# Loginator2368.net
KiCad netlist of a schematic drawn in EAGLE
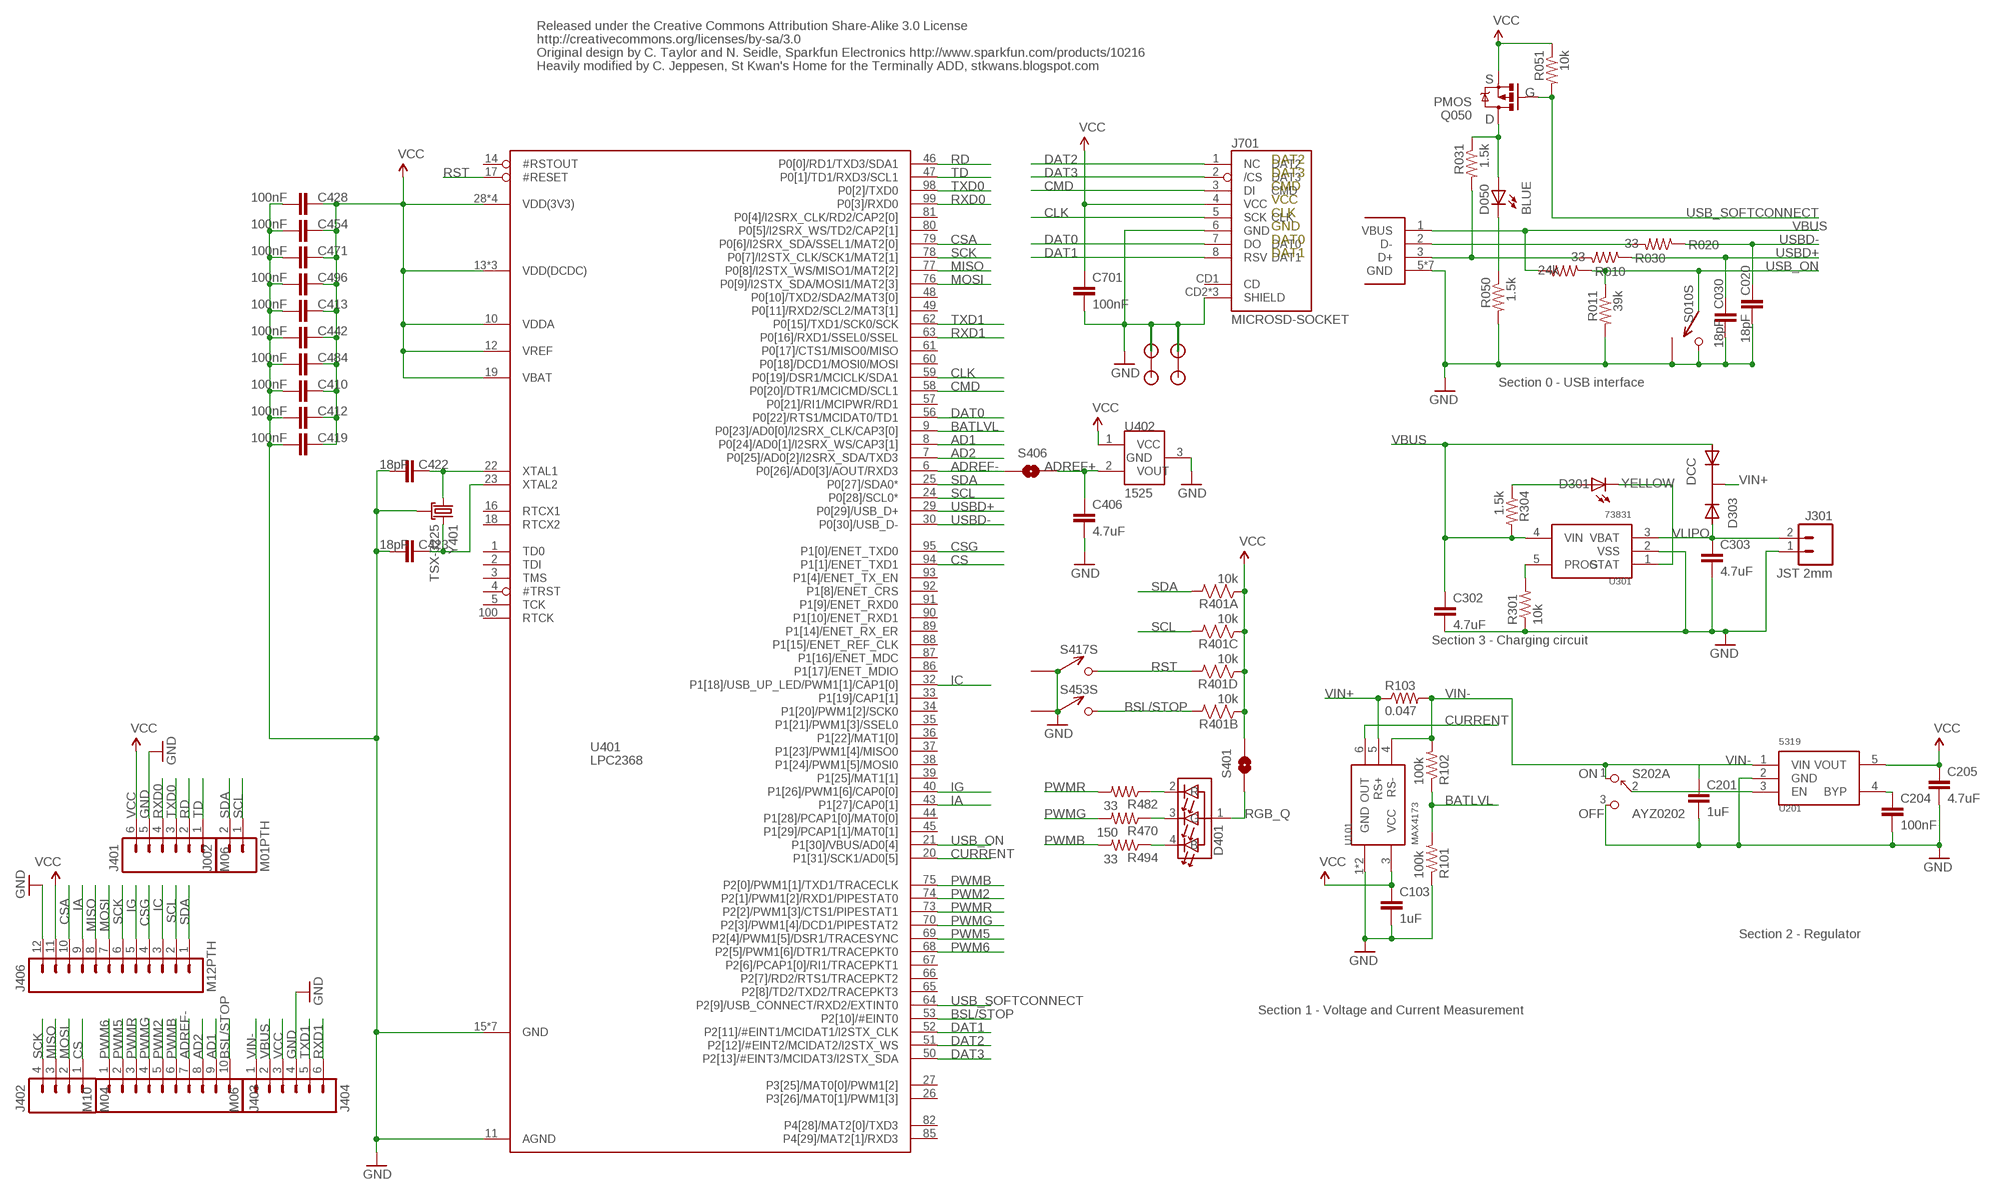
[diagram p0: schematic, sheet 1]

(export (version "E")
  (design (tool "Eeschema 10.0.6"))
  (components
    (comp (ref "C020")
      (value "18pF")
      (footprint "eagle-import:0402-CAP")
      (libsource (lib "eagle-import") (part "CAP0402-CAP"))
    )
    (comp (ref "C030")
      (value "18pF")
      (footprint "eagle-import:0402-CAP")
      (libsource (lib "eagle-import") (part "CAP0402-CAP"))
    )
    (comp (ref "C103")
      (value "1uF")
      (footprint "eagle-import:0402-CAP")
      (libsource (lib "eagle-import") (part "CAP0402-CAP"))
    )
    (comp (ref "C201")
      (value "1uF")
      (footprint "eagle-import:0402-CAP")
      (libsource (lib "eagle-import") (part "CAP0402-CAP"))
    )
    (comp (ref "C204")
      (value "100nF")
      (footprint "eagle-import:0402-CAP")
      (libsource (lib "eagle-import") (part "CAP0402-CAP"))
    )
    (comp (ref "C205")
      (value "4.7uF")
      (footprint "eagle-import:0402-CAP")
      (libsource (lib "eagle-import") (part "CAP0402-CAP"))
    )
    (comp (ref "C302")
      (value "4.7uF")
      (footprint "eagle-import:0402-CAP")
      (libsource (lib "eagle-import") (part "CAP0402-CAP"))
    )
    (comp (ref "C303")
      (value "4.7uF")
      (footprint "eagle-import:0402-CAP")
      (libsource (lib "eagle-import") (part "CAP0402-CAP"))
    )
    (comp (ref "C406")
      (value "4.7uF")
      (footprint "eagle-import:0402-CAP")
      (libsource (lib "eagle-import") (part "CAP0402-CAP"))
    )
    (comp (ref "C410")
      (value "100nF")
      (footprint "eagle-import:0402-CAP")
      (libsource (lib "eagle-import") (part "CAP0402-CAP"))
    )
    (comp (ref "C412")
      (value "100nF")
      (footprint "eagle-import:0402-CAP")
      (libsource (lib "eagle-import") (part "CAP0402-CAP"))
    )
    (comp (ref "C413")
      (value "100nF")
      (footprint "eagle-import:0402-CAP")
      (libsource (lib "eagle-import") (part "CAP0402-CAP"))
    )
    (comp (ref "C419")
      (value "100nF")
      (footprint "eagle-import:0402-CAP")
      (libsource (lib "eagle-import") (part "CAP0402-CAP"))
    )
    (comp (ref "C422")
      (value "18pF")
      (footprint "eagle-import:0402-CAP")
      (libsource (lib "eagle-import") (part "CAP0402-CAP"))
    )
    (comp (ref "C423")
      (value "18pF")
      (footprint "eagle-import:0402-CAP")
      (libsource (lib "eagle-import") (part "CAP0402-CAP"))
    )
    (comp (ref "C428")
      (value "100nF")
      (footprint "eagle-import:0402-CAP")
      (libsource (lib "eagle-import") (part "CAP0402-CAP"))
    )
    (comp (ref "C442")
      (value "100nF")
      (footprint "eagle-import:0402-CAP")
      (libsource (lib "eagle-import") (part "CAP0402-CAP"))
    )
    (comp (ref "C454")
      (value "100nF")
      (footprint "eagle-import:0402-CAP")
      (libsource (lib "eagle-import") (part "CAP0402-CAP"))
    )
    (comp (ref "C471")
      (value "100nF")
      (footprint "eagle-import:0402-CAP")
      (libsource (lib "eagle-import") (part "CAP0402-CAP"))
    )
    (comp (ref "C484")
      (value "100nF")
      (footprint "eagle-import:0402-CAP")
      (libsource (lib "eagle-import") (part "CAP0402-CAP"))
    )
    (comp (ref "C496")
      (value "100nF")
      (footprint "eagle-import:0402-CAP")
      (libsource (lib "eagle-import") (part "CAP0402-CAP"))
    )
    (comp (ref "C701")
      (value "100nF")
      (footprint "eagle-import:0402-CAP")
      (libsource (lib "eagle-import") (part "CAP0402-CAP"))
    )
    (comp (ref "D050")
      (value "BLUE")
      (footprint "eagle-import:LED-0603")
      (libsource (lib "eagle-import") (part "LED0603"))
    )
    (comp (ref "D301")
      (value "YELLOW")
      (footprint "eagle-import:LED-0603")
      (libsource (lib "eagle-import") (part "LED0603"))
    )
    (comp (ref "D303")
      (value "DCC")
      (footprint "eagle-import:SOT-23-3")
      (libsource (lib "eagle-import") (part "PMEG2005CT"))
    )
    (comp (ref "D401")
      (value "RGB")
      (footprint "eagle-import:HSMF-C118")
      (libsource (lib "eagle-import") (part "HSMF-C118"))
    )
    (comp (ref "J001")
      (value "USB_MICROB_JSTFCI")
      (footprint "eagle-import:USB-MICROB-CONN-09505")
      (libsource (lib "eagle-import") (part "USB_MICROB_JSTFCI"))
    )
    (comp (ref "J002")
      (value "M01PTH")
      (footprint "eagle-import:1X02")
      (libsource (lib "eagle-import") (part "M02PTH"))
    )
    (comp (ref "J301")
      (value "JST 2mm")
      (footprint "eagle-import:JST-2-SMD")
      (libsource (lib "eagle-import") (part "M02-JST-2MM-SMT"))
    )
    (comp (ref "J401")
      (value "M06")
      (footprint "eagle-import:1X06")
      (libsource (lib "eagle-import") (part "M06SIP"))
    )
    (comp (ref "J402")
      (value "M04")
      (footprint "eagle-import:1X04")
      (libsource (lib "eagle-import") (part "M04PTH"))
    )
    (comp (ref "J403")
      (value "M10")
      (footprint "eagle-import:1X10")
      (libsource (lib "eagle-import") (part "M10{dblquote}"))
    )
    (comp (ref "J404")
      (value "M06")
      (footprint "eagle-import:1X06")
      (libsource (lib "eagle-import") (part "M06SIP"))
    )
    (comp (ref "J406")
      (value "M12PTH")
      (footprint "eagle-import:1X12")
      (libsource (lib "eagle-import") (part "M12PTH"))
    )
    (comp (ref "J701")
      (value "MICROSD-SOCKET")
      (footprint "eagle-import:MICROSD-SOCKET-PP")
      (libsource (lib "eagle-import") (part "MICROSD-SOCKET"))
    )
    (comp (ref "JP1")
      (value "STANDOFF")
      (footprint "eagle-import:STANDOFF")
      (libsource (lib "eagle-import") (part "STANDOFF"))
    )
    (comp (ref "JP2")
      (value "STANDOFF")
      (footprint "eagle-import:STANDOFF")
      (libsource (lib "eagle-import") (part "STANDOFF"))
    )
    (comp (ref "JP3")
      (value "STANDOFF")
      (footprint "eagle-import:STANDOFF")
      (libsource (lib "eagle-import") (part "STANDOFF"))
    )
    (comp (ref "JP4")
      (value "STANDOFF")
      (footprint "eagle-import:STANDOFF")
      (libsource (lib "eagle-import") (part "STANDOFF"))
    )
    (comp (ref "Q050")
      (value "PMOS")
      (footprint "eagle-import:SOT23-3")
      (libsource (lib "eagle-import") (part "MOSFET-PCHANNELSMD"))
    )
    (comp (ref "R010")
      (value "24k")
      (footprint "eagle-import:0402-RES")
      (libsource (lib "eagle-import") (part "RESISTOR0402-RES"))
    )
    (comp (ref "R011")
      (value "39k")
      (footprint "eagle-import:0402-RES")
      (libsource (lib "eagle-import") (part "RESISTOR0402-RES"))
    )
    (comp (ref "R020")
      (value "33")
      (footprint "eagle-import:0402-RES")
      (libsource (lib "eagle-import") (part "RESISTOR0402-RES"))
    )
    (comp (ref "R030")
      (value "33")
      (footprint "eagle-import:0402-RES")
      (libsource (lib "eagle-import") (part "RESISTOR0402-RES"))
    )
    (comp (ref "R031")
      (value "1.5k")
      (footprint "eagle-import:0402-RES")
      (libsource (lib "eagle-import") (part "RESISTOR0402-RES"))
    )
    (comp (ref "R050")
      (value "1.5k")
      (footprint "eagle-import:0402-RES")
      (libsource (lib "eagle-import") (part "RESISTOR0402-RES"))
    )
    (comp (ref "R051")
      (value "10k")
      (footprint "eagle-import:0402-RES")
      (libsource (lib "eagle-import") (part "RESISTOR0402-RES"))
    )
    (comp (ref "R101")
      (value "100k")
      (footprint "eagle-import:0402-RES")
      (libsource (lib "eagle-import") (part "RESISTOR0402-RES"))
    )
    (comp (ref "R102")
      (value "100k")
      (footprint "eagle-import:0402-RES")
      (libsource (lib "eagle-import") (part "RESISTOR0402-RES"))
    )
    (comp (ref "R103")
      (value "0.047")
      (footprint "eagle-import:0402-RES")
      (libsource (lib "eagle-import") (part "RESISTOR0402-RES"))
    )
    (comp (ref "R301")
      (value "10k")
      (footprint "eagle-import:0402-RES")
      (libsource (lib "eagle-import") (part "RESISTOR0402-RES"))
    )
    (comp (ref "R304")
      (value "1.5k")
      (footprint "eagle-import:0402-RES")
      (libsource (lib "eagle-import") (part "RESISTOR0402-RES"))
    )
    (comp (ref "R401")
      (value "10k")
      (footprint "eagle-import:CRA04")
      (fields (field (name "DIGIKEY") "CRA4S810KCT-ND"))
      (libsource (lib "eagle-import") (part "RP404"))
    )
    (comp (ref "R470")
      (value "150")
      (footprint "eagle-import:0402-RES")
      (libsource (lib "eagle-import") (part "RESISTOR0402-RES"))
    )
    (comp (ref "R482")
      (value "33")
      (footprint "eagle-import:0402-RES")
      (libsource (lib "eagle-import") (part "RESISTOR0402-RES"))
    )
    (comp (ref "R494")
      (value "33")
      (footprint "eagle-import:0402-RES")
      (libsource (lib "eagle-import") (part "RESISTOR0402-RES"))
    )
    (comp (ref "S010")
      (value "SPST")
      (footprint "eagle-import:B3U-1100P")
      (fields (field (name "DIGIKEY") "SW1021CT-ND"))
      (libsource (lib "eagle-import") (part "B3U-1100P"))
    )
    (comp (ref "S202")
      (value "AYZ0202")
      (footprint "eagle-import:AYZ0202")
      (libsource (lib "eagle-import") (part "AYZ0202"))
    )
    (comp (ref "S401")
      (value "SOLDERJUMPERNO")
      (footprint "eagle-import:SJ_2S-NO")
      (libsource (lib "eagle-import") (part "SOLDERJUMPERNO"))
    )
    (comp (ref "S406")
      (value "SOLDERJUMPERNO")
      (footprint "eagle-import:SJ_2S-NO")
      (libsource (lib "eagle-import") (part "SOLDERJUMPERNO"))
    )
    (comp (ref "S417")
      (value "SPST")
      (footprint "eagle-import:B3U-1100P")
      (fields (field (name "DIGIKEY") "SW1021CT-ND"))
      (libsource (lib "eagle-import") (part "B3U-1100P"))
    )
    (comp (ref "S453")
      (value "SPST")
      (footprint "eagle-import:B3U-1100P")
      (fields (field (name "DIGIKEY") "SW1021CT-ND"))
      (libsource (lib "eagle-import") (part "B3U-1100P"))
    )
    (comp (ref "U101")
      (value "MAX4173")
      (footprint "eagle-import:SOT-23-6")
      (libsource (lib "eagle-import") (part "MAX4173"))
    )
    (comp (ref "U201")
      (value "5319")
      (footprint "eagle-import:SOT-23-5")
      (libsource (lib "eagle-import") (part "MIC5319D5"))
    )
    (comp (ref "U301")
      (value "73831")
      (footprint "eagle-import:SOT-23-5")
      (libsource (lib "eagle-import") (part "MCP73831"))
    )
    (comp (ref "U401")
      (value "LPC2368")
      (footprint "eagle-import:LQFP100")
      (libsource (lib "eagle-import") (part "LPC2368"))
    )
    (comp (ref "U402")
      (value "1525")
      (footprint "eagle-import:SOT-23-3")
      (libsource (lib "eagle-import") (part "MCP1525"))
    )
    (comp (ref "Y401")
      (value "TSX-3225")
      (footprint "eagle-import:CRYSTAL_SMD")
      (libsource (lib "eagle-import") (part "TSX-3225"))
    )
  )
  (nets
    (net (code "1") (name "/AD1") (class "Default")
      (node (ref "J403") (pin "9") (pinfunction "9_9") (pintype "passive"))
      (node (ref "U401") (pin "8") (pinfunction "P0[24]/AD0[1]/I2SRX_WS/CAP3[1]_8") (pintype "bidirectional"))
    )
    (net (code "2") (name "/AD2") (class "Default")
      (node (ref "J403") (pin "8") (pinfunction "8_8") (pintype "passive"))
      (node (ref "U401") (pin "7") (pinfunction "P0[25]/AD0[2]/I2SRX_SDA/TXD3_7") (pintype "bidirectional"))
    )
    (net (code "3") (name "/ADREF+") (class "Default")
      (node (ref "C406") (pin "1") (pinfunction "1_1") (pintype "passive"))
      (node (ref "S406") (pin "1") (pinfunction "1_1") (pintype "passive"))
      (node (ref "U402") (pin "2") (pinfunction "VOUT_2") (pintype "bidirectional"))
    )
    (net (code "4") (name "/ADREF-") (class "Default")
      (node (ref "J403") (pin "7") (pinfunction "7_7") (pintype "passive"))
      (node (ref "S406") (pin "2") (pinfunction "2_2") (pintype "passive"))
      (node (ref "U401") (pin "6") (pinfunction "P0[26]/AD0[3]/AOUT/RXD3_6") (pintype "bidirectional"))
    )
    (net (code "5") (name "/BATLVL") (class "Default")
      (node (ref "R101") (pin "2") (pinfunction "2_2") (pintype "passive"))
      (node (ref "R102") (pin "1") (pinfunction "1_1") (pintype "passive"))
      (node (ref "U401") (pin "9") (pinfunction "P0[23]/AD0[0]/I2SRX_CLK/CAP3[0]_9") (pintype "bidirectional"))
    )
    (net (code "6") (name "/BSL{slash}STOP") (class "Default")
      (node (ref "J403") (pin "10") (pinfunction "10_10") (pintype "passive"))
      (node (ref "R401") (pin "7") (pinfunction "2_7") (pintype "passive"))
      (node (ref "S453") (pin "P$2") (pinfunction "2_P$2") (pintype "bidirectional"))
      (node (ref "U401") (pin "53") (pinfunction "P2[10]/#EINT0_53") (pintype "bidirectional"))
    )
    (net (code "7") (name "/CLK") (class "Default")
      (node (ref "J701") (pin "5") (pinfunction "SCK_5") (pintype "bidirectional"))
      (node (ref "U401") (pin "59") (pinfunction "P0[19]/DSR1/MCICLK/SDA1_59") (pintype "bidirectional"))
    )
    (net (code "8") (name "/CMD") (class "Default")
      (node (ref "J701") (pin "3") (pinfunction "DI_3") (pintype "bidirectional"))
      (node (ref "U401") (pin "58") (pinfunction "P0[20]/DTR1/MCICMD/SCL1_58") (pintype "bidirectional"))
    )
    (net (code "9") (name "/CS") (class "Default")
      (node (ref "J402") (pin "1") (pinfunction "1_1") (pintype "passive"))
      (node (ref "U401") (pin "94") (pinfunction "P1[1]/ENET_TXD1_94") (pintype "bidirectional"))
    )
    (net (code "10") (name "/CSA") (class "Default")
      (node (ref "J406") (pin "10") (pinfunction "10_10") (pintype "passive"))
      (node (ref "U401") (pin "79") (pinfunction "P0[6]/I2SRX_SDA/SSEL1/MAT2[0]_79") (pintype "bidirectional"))
    )
    (net (code "11") (name "/CSG") (class "Default")
      (node (ref "J406") (pin "4") (pinfunction "4_4") (pintype "passive"))
      (node (ref "U401") (pin "95") (pinfunction "P1[0]/ENET_TXD0_95") (pintype "bidirectional"))
    )
    (net (code "12") (name "/CURRENT") (class "Default")
      (node (ref "U101") (pin "6") (pinfunction "OUT_6") (pintype "bidirectional"))
      (node (ref "U401") (pin "20") (pinfunction "P1[31]/SCK1/AD0[5]_20") (pintype "bidirectional"))
    )
    (net (code "13") (name "/DAT0") (class "Default")
      (node (ref "J701") (pin "7") (pinfunction "DO_7") (pintype "bidirectional"))
      (node (ref "U401") (pin "56") (pinfunction "P0[22]/RTS1/MCIDAT0/TD1_56") (pintype "bidirectional"))
    )
    (net (code "14") (name "/DAT1") (class "Default")
      (node (ref "J701") (pin "8") (pinfunction "RSV_8") (pintype "bidirectional"))
      (node (ref "U401") (pin "52") (pinfunction "P2[11]/#EINT1/MCIDAT1/I2STX_CLK_52") (pintype "bidirectional"))
    )
    (net (code "15") (name "/DAT2") (class "Default")
      (node (ref "J701") (pin "1") (pinfunction "NC_1") (pintype "bidirectional"))
      (node (ref "U401") (pin "51") (pinfunction "P2[12]/#EINT2/MCIDAT2/I2STX_WS_51") (pintype "bidirectional"))
    )
    (net (code "16") (name "/DAT3") (class "Default")
      (node (ref "J701") (pin "2") (pinfunction "/CS_2") (pintype "bidirectional"))
      (node (ref "U401") (pin "50") (pinfunction "P2[13]/#EINT3/MCIDAT3/I2STX_SDA_50") (pintype "bidirectional"))
    )
    (net (code "17") (name "/IA") (class "Default")
      (node (ref "J406") (pin "9") (pinfunction "9_9") (pintype "passive"))
      (node (ref "U401") (pin "43") (pinfunction "P1[27]/CAP0[1]_43") (pintype "bidirectional"))
    )
    (net (code "18") (name "/IC") (class "Default")
      (node (ref "J406") (pin "3") (pinfunction "3_3") (pintype "passive"))
      (node (ref "U401") (pin "32") (pinfunction "P1[18]/USB_UP_LED/PWM1[1]/CAP1[0]_32") (pintype "bidirectional"))
    )
    (net (code "19") (name "/IG") (class "Default")
      (node (ref "J406") (pin "5") (pinfunction "5_5") (pintype "passive"))
      (node (ref "U401") (pin "40") (pinfunction "P1[26]/PWM1[6]/CAP0[0]_40") (pintype "bidirectional"))
    )
    (net (code "20") (name "/MISO") (class "Default")
      (node (ref "J402") (pin "3") (pinfunction "3_3") (pintype "passive"))
      (node (ref "J406") (pin "8") (pinfunction "8_8") (pintype "passive"))
      (node (ref "U401") (pin "77") (pinfunction "P0[8]/I2STX_WS/MISO1/MAT2[2]_77") (pintype "bidirectional"))
    )
    (net (code "21") (name "/MOSI") (class "Default")
      (node (ref "J402") (pin "2") (pinfunction "2_2") (pintype "passive"))
      (node (ref "J406") (pin "7") (pinfunction "7_7") (pintype "passive"))
      (node (ref "U401") (pin "76") (pinfunction "P0[9]/I2STX_SDA/MOSI1/MAT2[3]_76") (pintype "bidirectional"))
    )
    (net (code "22") (name "/PWM2") (class "Default")
      (node (ref "J403") (pin "5") (pinfunction "5_5") (pintype "passive"))
      (node (ref "U401") (pin "74") (pinfunction "P2[1]/PWM1[2]/RXD1/PIPESTAT0_74") (pintype "bidirectional"))
    )
    (net (code "23") (name "/PWM5") (class "Default")
      (node (ref "J403") (pin "2") (pinfunction "2_2") (pintype "passive"))
      (node (ref "U401") (pin "69") (pinfunction "P2[4]/PWM1[5]/DSR1/TRACESYNC_69") (pintype "bidirectional"))
    )
    (net (code "24") (name "/PWM6") (class "Default")
      (node (ref "J403") (pin "1") (pinfunction "1_1") (pintype "passive"))
      (node (ref "U401") (pin "68") (pinfunction "P2[5]/PWM1[6]/DTR1/TRACEPKT0_68") (pintype "bidirectional"))
    )
    (net (code "25") (name "/PWMB") (class "Default")
      (node (ref "J403") (pin "6") (pinfunction "6_6") (pintype "passive"))
      (node (ref "R494") (pin "2") (pinfunction "2_2") (pintype "passive"))
      (node (ref "U401") (pin "75") (pinfunction "P2[0]/PWM1[1]/TXD1/TRACECLK_75") (pintype "bidirectional"))
    )
    (net (code "26") (name "/PWMG") (class "Default")
      (node (ref "J403") (pin "4") (pinfunction "4_4") (pintype "passive"))
      (node (ref "R470") (pin "2") (pinfunction "2_2") (pintype "passive"))
      (node (ref "U401") (pin "70") (pinfunction "P2[3]/PWM1[4]/DCD1/PIPESTAT2_70") (pintype "bidirectional"))
    )
    (net (code "27") (name "/PWMR") (class "Default")
      (node (ref "J403") (pin "3") (pinfunction "3_3") (pintype "passive"))
      (node (ref "R482") (pin "2") (pinfunction "2_2") (pintype "passive"))
      (node (ref "U401") (pin "73") (pinfunction "P2[2]/PWM1[3]/CTS1/PIPESTAT1_73") (pintype "bidirectional"))
    )
    (net (code "28") (name "/RD") (class "Default")
      (node (ref "J401") (pin "2") (pinfunction "2_2") (pintype "passive"))
      (node (ref "U401") (pin "46") (pinfunction "P0[0]/RD1/TXD3/SDA1_46") (pintype "bidirectional"))
    )
    (net (code "29") (name "/RGB_Q") (class "Default")
      (node (ref "D401") (pin "1") (pinfunction "A_1") (pintype "passive"))
      (node (ref "S401") (pin "1") (pinfunction "1_1") (pintype "passive"))
    )
    (net (code "30") (name "/RST") (class "Default")
      (node (ref "R401") (pin "5") (pinfunction "2_5") (pintype "passive"))
      (node (ref "S417") (pin "P$2") (pinfunction "2_P$2") (pintype "bidirectional"))
      (node (ref "U401") (pin "17") (pinfunction "#RESET_17") (pintype "bidirectional"))
    )
    (net (code "31") (name "/RXD0") (class "Default")
      (node (ref "J401") (pin "4") (pinfunction "4_4") (pintype "passive"))
      (node (ref "U401") (pin "99") (pinfunction "P0[3]/RXD0_99") (pintype "bidirectional"))
    )
    (net (code "32") (name "/RXD1") (class "Default")
      (node (ref "J404") (pin "6") (pinfunction "6_6") (pintype "passive"))
      (node (ref "U401") (pin "63") (pinfunction "P0[16]/RXD1/SSEL0/SSEL_63") (pintype "bidirectional"))
    )
    (net (code "33") (name "/SCK") (class "Default")
      (node (ref "J402") (pin "4") (pinfunction "4_4") (pintype "passive"))
      (node (ref "J406") (pin "6") (pinfunction "6_6") (pintype "passive"))
      (node (ref "U401") (pin "78") (pinfunction "P0[7]/I2STX_CLK/SCK1/MAT2[1]_78") (pintype "bidirectional"))
    )
    (net (code "34") (name "/SCL") (class "Default")
      (node (ref "J002") (pin "1") (pinfunction "1_1") (pintype "passive"))
      (node (ref "J406") (pin "2") (pinfunction "2_2") (pintype "passive"))
      (node (ref "R401") (pin "6") (pinfunction "2_6") (pintype "passive"))
      (node (ref "U401") (pin "24") (pinfunction "P0[28]/SCL0*_24") (pintype "bidirectional"))
    )
    (net (code "35") (name "/SDA") (class "Default")
      (node (ref "J002") (pin "2") (pinfunction "2_2") (pintype "passive"))
      (node (ref "J406") (pin "1") (pinfunction "1_1") (pintype "passive"))
      (node (ref "R401") (pin "8") (pinfunction "2_8") (pintype "passive"))
      (node (ref "U401") (pin "25") (pinfunction "P0[27]/SDA0*_25") (pintype "bidirectional"))
    )
    (net (code "36") (name "/TD") (class "Default")
      (node (ref "J401") (pin "1") (pinfunction "1_1") (pintype "passive"))
      (node (ref "U401") (pin "47") (pinfunction "P0[1]/TD1/RXD3/SCL1_47") (pintype "bidirectional"))
    )
    (net (code "37") (name "/TXD0") (class "Default")
      (node (ref "J401") (pin "3") (pinfunction "3_3") (pintype "passive"))
      (node (ref "U401") (pin "98") (pinfunction "P0[2]/TXD0_98") (pintype "bidirectional"))
    )
    (net (code "38") (name "/TXD1") (class "Default")
      (node (ref "J404") (pin "5") (pinfunction "5_5") (pintype "passive"))
      (node (ref "U401") (pin "62") (pinfunction "P0[15]/TXD1/SCK0/SCK_62") (pintype "bidirectional"))
    )
    (net (code "39") (name "/USBD+") (class "Default")
      (node (ref "C030") (pin "1") (pinfunction "1_1") (pintype "passive"))
      (node (ref "R030") (pin "1") (pinfunction "1_1") (pintype "passive"))
      (node (ref "U401") (pin "29") (pinfunction "P0[29]/USB_D+_29") (pintype "bidirectional"))
    )
    (net (code "40") (name "/USBD-") (class "Default")
      (node (ref "C020") (pin "1") (pinfunction "1_1") (pintype "passive"))
      (node (ref "R020") (pin "1") (pinfunction "1_1") (pintype "passive"))
      (node (ref "U401") (pin "30") (pinfunction "P0[30]/USB_D-_30") (pintype "bidirectional"))
    )
    (net (code "41") (name "/USB_ON") (class "Default")
      (node (ref "R010") (pin "1") (pinfunction "1_1") (pintype "passive"))
      (node (ref "R011") (pin "1") (pinfunction "1_1") (pintype "passive"))
      (node (ref "S010") (pin "P$1") (pinfunction "1_P$1") (pintype "bidirectional"))
      (node (ref "U401") (pin "21") (pinfunction "P1[30]/VBUS/AD0[4]_21") (pintype "bidirectional"))
    )
    (net (code "42") (name "/USB_SOFTCONNECT") (class "Default")
      (node (ref "Q050") (pin "1") (pinfunction "G_1") (pintype "passive"))
      (node (ref "R051") (pin "2") (pinfunction "2_2") (pintype "passive"))
      (node (ref "U401") (pin "64") (pinfunction "P2[9]/USB_CONNECT/RXD2/EXTINT0_64") (pintype "bidirectional"))
    )
    (net (code "43") (name "/VBUS") (class "Default")
      (node (ref "C302") (pin "1") (pinfunction "1_1") (pintype "passive"))
      (node (ref "D303") (pin "1") (pinfunction "A1_1") (pintype "passive"))
      (node (ref "J001") (pin "1") (pinfunction "VBUS_1") (pintype "bidirectional"))
      (node (ref "J404") (pin "2") (pinfunction "2_2") (pintype "passive"))
      (node (ref "R010") (pin "2") (pinfunction "2_2") (pintype "passive"))
      (node (ref "R304") (pin "2") (pinfunction "2_2") (pintype "passive"))
      (node (ref "U301") (pin "4") (pinfunction "VIN_4") (pintype "power_in"))
    )
    (net (code "44") (name "/VIN+") (class "Default")
      (node (ref "D303") (pin "3") (pinfunction "K_3") (pintype "passive"))
      (node (ref "R103") (pin "1") (pinfunction "1_1") (pintype "passive"))
      (node (ref "U101") (pin "5") (pinfunction "RS+_5") (pintype "bidirectional"))
    )
    (net (code "45") (name "/VIN-") (class "Default")
      (node (ref "C201") (pin "1") (pinfunction "1_1") (pintype "passive"))
      (node (ref "J404") (pin "1") (pinfunction "1_1") (pintype "passive"))
      (node (ref "R102") (pin "2") (pinfunction "2_2") (pintype "passive"))
      (node (ref "R103") (pin "2") (pinfunction "2_2") (pintype "passive"))
      (node (ref "S202") (pin "1") (pinfunction "P$1_1") (pintype "bidirectional"))
      (node (ref "U101") (pin "4") (pinfunction "RS-_4") (pintype "bidirectional"))
      (node (ref "U201") (pin "1") (pinfunction "VIN_1") (pintype "bidirectional"))
    )
    (net (code "46") (name "/VLIPO") (class "Default")
      (node (ref "C303") (pin "1") (pinfunction "1_1") (pintype "passive"))
      (node (ref "D303") (pin "2") (pinfunction "A2_2") (pintype "passive"))
      (node (ref "J301") (pin "2") (pinfunction "2_2") (pintype "passive"))
      (node (ref "U301") (pin "3") (pinfunction "VBAT_3") (pintype "power_in"))
    )
    (net (code "47") (name "GND") (class "Default")
      (node (ref "C020") (pin "2") (pinfunction "2_2") (pintype "passive"))
      (node (ref "C030") (pin "2") (pinfunction "2_2") (pintype "passive"))
      (node (ref "C103") (pin "2") (pinfunction "2_2") (pintype "passive"))
      (node (ref "C201") (pin "2") (pinfunction "2_2") (pintype "passive"))
      (node (ref "C204") (pin "2") (pinfunction "2_2") (pintype "passive"))
      (node (ref "C205") (pin "2") (pinfunction "2_2") (pintype "passive"))
      (node (ref "C302") (pin "2") (pinfunction "2_2") (pintype "passive"))
      (node (ref "C303") (pin "2") (pinfunction "2_2") (pintype "passive"))
      (node (ref "C406") (pin "2") (pinfunction "2_2") (pintype "passive"))
      (node (ref "C410") (pin "2") (pinfunction "2_2") (pintype "passive"))
      (node (ref "C412") (pin "2") (pinfunction "2_2") (pintype "passive"))
      (node (ref "C413") (pin "2") (pinfunction "2_2") (pintype "passive"))
      (node (ref "C419") (pin "2") (pinfunction "2_2") (pintype "passive"))
      (node (ref "C422") (pin "1") (pinfunction "1_1") (pintype "passive"))
      (node (ref "C423") (pin "1") (pinfunction "1_1") (pintype "passive"))
      (node (ref "C428") (pin "2") (pinfunction "2_2") (pintype "passive"))
      (node (ref "C442") (pin "2") (pinfunction "2_2") (pintype "passive"))
      (node (ref "C454") (pin "2") (pinfunction "2_2") (pintype "passive"))
      (node (ref "C471") (pin "2") (pinfunction "2_2") (pintype "passive"))
      (node (ref "C484") (pin "2") (pinfunction "2_2") (pintype "passive"))
      (node (ref "C496") (pin "2") (pinfunction "2_2") (pintype "passive"))
      (node (ref "C701") (pin "2") (pinfunction "2_2") (pintype "passive"))
      (node (ref "J001") (pin "5") (pinfunction "GND_5") (pintype "bidirectional"))
      (node (ref "J001") (pin "P1") (pinfunction "GND_P1") (pintype "bidirectional"))
      (node (ref "J001") (pin "P2") (pinfunction "GND_P2") (pintype "bidirectional"))
      (node (ref "J001") (pin "P3") (pinfunction "GND_P3") (pintype "bidirectional"))
      (node (ref "J001") (pin "P4") (pinfunction "GND_P4") (pintype "bidirectional"))
      (node (ref "J001") (pin "P5") (pinfunction "GND_P5") (pintype "bidirectional"))
      (node (ref "J001") (pin "P6") (pinfunction "GND_P6") (pintype "bidirectional"))
      (node (ref "J301") (pin "1") (pinfunction "1_1") (pintype "passive"))
      (node (ref "J401") (pin "5") (pinfunction "5_5") (pintype "passive"))
      (node (ref "J404") (pin "4") (pinfunction "4_4") (pintype "passive"))
      (node (ref "J406") (pin "12") (pinfunction "12_12") (pintype "passive"))
      (node (ref "J701") (pin "6") (pinfunction "GND_6") (pintype "bidirectional"))
      (node (ref "J701") (pin "CD2") (pinfunction "SHIELD_CD2") (pintype "bidirectional"))
      (node (ref "J701") (pin "GND1") (pinfunction "SHIELD_GND1") (pintype "bidirectional"))
      (node (ref "J701") (pin "GND3") (pinfunction "SHIELD_GND3") (pintype "bidirectional"))
      (node (ref "JP1") (pin "P$1") (pinfunction "P$1_P$1") (pintype "bidirectional"))
      (node (ref "JP2") (pin "P$1") (pinfunction "P$1_P$1") (pintype "bidirectional"))
      (node (ref "JP3") (pin "P$1") (pinfunction "P$1_P$1") (pintype "bidirectional"))
      (node (ref "JP4") (pin "P$1") (pinfunction "P$1_P$1") (pintype "bidirectional"))
      (node (ref "R011") (pin "2") (pinfunction "2_2") (pintype "passive"))
      (node (ref "R050") (pin "2") (pinfunction "2_2") (pintype "passive"))
      (node (ref "R101") (pin "1") (pinfunction "1_1") (pintype "passive"))
      (node (ref "R301") (pin "1") (pinfunction "1_1") (pintype "passive"))
      (node (ref "S010") (pin "P$2") (pinfunction "2_P$2") (pintype "bidirectional"))
      (node (ref "S010") (pin "P$3") (pinfunction "1_P$3") (pintype "bidirectional"))
      (node (ref "S202") (pin "3") (pinfunction "P$2_3") (pintype "bidirectional"))
      (node (ref "S417") (pin "P$1") (pinfunction "1_P$1") (pintype "bidirectional"))
      (node (ref "S417") (pin "P$3") (pinfunction "1_P$3") (pintype "bidirectional"))
      (node (ref "S453") (pin "P$1") (pinfunction "1_P$1") (pintype "bidirectional"))
      (node (ref "S453") (pin "P$3") (pinfunction "1_P$3") (pintype "bidirectional"))
      (node (ref "U101") (pin "1") (pinfunction "GND_1") (pintype "bidirectional"))
      (node (ref "U101") (pin "2") (pinfunction "GND_2") (pintype "bidirectional"))
      (node (ref "U201") (pin "2") (pinfunction "GND_2") (pintype "bidirectional"))
      (node (ref "U301") (pin "2") (pinfunction "VSS_2") (pintype "power_in"))
      (node (ref "U401") (pin "11") (pinfunction "AGND_11") (pintype "bidirectional"))
      (node (ref "U401") (pin "15") (pinfunction "GND_15") (pintype "bidirectional"))
      (node (ref "U401") (pin "31") (pinfunction "GND_31") (pintype "bidirectional"))
      (node (ref "U401") (pin "41") (pinfunction "GND_41") (pintype "bidirectional"))
      (node (ref "U401") (pin "55") (pinfunction "GND_55") (pintype "bidirectional"))
      (node (ref "U401") (pin "72") (pinfunction "GND_72") (pintype "bidirectional"))
      (node (ref "U401") (pin "83") (pinfunction "GND_83") (pintype "bidirectional"))
      (node (ref "U401") (pin "97") (pinfunction "GND_97") (pintype "bidirectional"))
      (node (ref "U402") (pin "3") (pinfunction "GND_3") (pintype "bidirectional"))
      (node (ref "Y401") (pin "2") (pinfunction "GND_2") (pintype "passive"))
      (node (ref "Y401") (pin "4") (pinfunction "GND_4") (pintype "passive"))
    )
    (net (code "48") (name "Net-(D050-PadC)") (class "Default")
      (node (ref "D050") (pin "C") (pinfunction "C_C") (pintype "passive"))
      (node (ref "R050") (pin "1") (pinfunction "1_1") (pintype "passive"))
    )
    (net (code "49") (name "Net-(D301-PadA)") (class "Default")
      (node (ref "D301") (pin "A") (pinfunction "A_A") (pintype "passive"))
      (node (ref "R304") (pin "1") (pinfunction "1_1") (pintype "passive"))
    )
    (net (code "50") (name "Net-(D401-B)") (class "Default")
      (node (ref "D401") (pin "4") (pinfunction "B_4") (pintype "passive"))
      (node (ref "R494") (pin "1") (pinfunction "1_1") (pintype "passive"))
    )
    (net (code "51") (name "Net-(D401-G)") (class "Default")
      (node (ref "D401") (pin "3") (pinfunction "G_3") (pintype "passive"))
      (node (ref "R470") (pin "1") (pinfunction "1_1") (pintype "passive"))
    )
    (net (code "52") (name "Net-(D401-R)") (class "Default")
      (node (ref "D401") (pin "2") (pinfunction "R_2") (pintype "passive"))
      (node (ref "R482") (pin "1") (pinfunction "1_1") (pintype "passive"))
    )
    (net (code "53") (name "Net-(J001-D+)") (class "Default")
      (node (ref "J001") (pin "3") (pinfunction "D+_3") (pintype "bidirectional"))
      (node (ref "R030") (pin "2") (pinfunction "2_2") (pintype "passive"))
      (node (ref "R031") (pin "2") (pinfunction "2_2") (pintype "passive"))
    )
    (net (code "54") (name "Net-(J001-D-)") (class "Default")
      (node (ref "J001") (pin "2") (pinfunction "D-_2") (pintype "bidirectional"))
      (node (ref "R020") (pin "2") (pinfunction "2_2") (pintype "passive"))
    )
    (net (code "55") (name "Net-(Q050-D)") (class "Default")
      (node (ref "D050") (pin "A") (pinfunction "A_A") (pintype "passive"))
      (node (ref "Q050") (pin "3") (pinfunction "D_3") (pintype "passive"))
      (node (ref "R031") (pin "1") (pinfunction "1_1") (pintype "passive"))
    )
    (net (code "56") (name "Net-(S202A-P$3)") (class "Default")
      (node (ref "S202") (pin "2") (pinfunction "P$3_2") (pintype "bidirectional"))
      (node (ref "U201") (pin "3") (pinfunction "EN_3") (pintype "bidirectional"))
    )
    (net (code "57") (name "Net-(U201-BYP)") (class "Default")
      (node (ref "C204") (pin "1") (pinfunction "1_1") (pintype "passive"))
      (node (ref "U201") (pin "4") (pinfunction "BYP_4") (pintype "bidirectional"))
    )
    (net (code "58") (name "Net-(U301-PROG)") (class "Default")
      (node (ref "R301") (pin "2") (pinfunction "2_2") (pintype "passive"))
      (node (ref "U301") (pin "5") (pinfunction "PROG_5") (pintype "passive"))
    )
    (net (code "59") (name "Net-(U301-STAT)") (class "Default")
      (node (ref "D301") (pin "C") (pinfunction "C_C") (pintype "passive"))
      (node (ref "U301") (pin "1") (pinfunction "STAT_1") (pintype "bidirectional"))
    )
    (net (code "60") (name "Net-(U401-XTAL1)") (class "Default")
      (node (ref "C422") (pin "2") (pinfunction "2_2") (pintype "passive"))
      (node (ref "U401") (pin "22") (pinfunction "XTAL1_22") (pintype "bidirectional"))
      (node (ref "Y401") (pin "1") (pinfunction "1_1") (pintype "passive"))
    )
    (net (code "61") (name "Net-(U401-XTAL2)") (class "Default")
      (node (ref "C423") (pin "2") (pinfunction "2_2") (pintype "passive"))
      (node (ref "U401") (pin "23") (pinfunction "XTAL2_23") (pintype "bidirectional"))
      (node (ref "Y401") (pin "3") (pinfunction "2_3") (pintype "passive"))
    )
    (net (code "62") (name "VCC") (class "Default")
      (node (ref "C103") (pin "1") (pinfunction "1_1") (pintype "passive"))
      (node (ref "C205") (pin "1") (pinfunction "1_1") (pintype "passive"))
      (node (ref "C410") (pin "1") (pinfunction "1_1") (pintype "passive"))
      (node (ref "C412") (pin "1") (pinfunction "1_1") (pintype "passive"))
      (node (ref "C413") (pin "1") (pinfunction "1_1") (pintype "passive"))
      (node (ref "C419") (pin "1") (pinfunction "1_1") (pintype "passive"))
      (node (ref "C428") (pin "1") (pinfunction "1_1") (pintype "passive"))
      (node (ref "C442") (pin "1") (pinfunction "1_1") (pintype "passive"))
      (node (ref "C454") (pin "1") (pinfunction "1_1") (pintype "passive"))
      (node (ref "C471") (pin "1") (pinfunction "1_1") (pintype "passive"))
      (node (ref "C484") (pin "1") (pinfunction "1_1") (pintype "passive"))
      (node (ref "C496") (pin "1") (pinfunction "1_1") (pintype "passive"))
      (node (ref "C701") (pin "1") (pinfunction "1_1") (pintype "passive"))
      (node (ref "J401") (pin "6") (pinfunction "6_6") (pintype "passive"))
      (node (ref "J404") (pin "3") (pinfunction "3_3") (pintype "passive"))
      (node (ref "J406") (pin "11") (pinfunction "11_11") (pintype "passive"))
      (node (ref "J701") (pin "4") (pinfunction "VCC_4") (pintype "bidirectional"))
      (node (ref "Q050") (pin "2") (pinfunction "S_2") (pintype "passive"))
      (node (ref "R051") (pin "1") (pinfunction "1_1") (pintype "passive"))
      (node (ref "R401") (pin "1") (pinfunction "1_1") (pintype "passive"))
      (node (ref "R401") (pin "2") (pinfunction "1_2") (pintype "passive"))
      (node (ref "R401") (pin "3") (pinfunction "1_3") (pintype "passive"))
      (node (ref "R401") (pin "4") (pinfunction "1_4") (pintype "passive"))
      (node (ref "S401") (pin "2") (pinfunction "2_2") (pintype "passive"))
      (node (ref "U101") (pin "3") (pinfunction "VCC_3") (pintype "bidirectional"))
      (node (ref "U201") (pin "5") (pinfunction "VOUT_5") (pintype "bidirectional"))
      (node (ref "U401") (pin "10") (pinfunction "VDDA_10") (pintype "bidirectional"))
      (node (ref "U401") (pin "12") (pinfunction "VREF_12") (pintype "bidirectional"))
      (node (ref "U401") (pin "13") (pinfunction "VDD(DCDC)_13") (pintype "bidirectional"))
      (node (ref "U401") (pin "19") (pinfunction "VBAT_19") (pintype "bidirectional"))
      (node (ref "U401") (pin "28") (pinfunction "VDD(3V3)_28") (pintype "bidirectional"))
      (node (ref "U401") (pin "42") (pinfunction "VDD(DCDC)_42") (pintype "bidirectional"))
      (node (ref "U401") (pin "54") (pinfunction "VDD(3V3)_54") (pintype "bidirectional"))
      (node (ref "U401") (pin "71") (pinfunction "VDD(3V3)_71") (pintype "bidirectional"))
      (node (ref "U401") (pin "84") (pinfunction "VDD(DCDC)_84") (pintype "bidirectional"))
      (node (ref "U401") (pin "96") (pinfunction "VDD(3V3)_96") (pintype "bidirectional"))
      (node (ref "U402") (pin "1") (pinfunction "VCC_1") (pintype "bidirectional"))
    )
    (net (code "63") (name "unconnected-(J701-CD-PadCD1)") (class "Default")
      (node (ref "J701") (pin "CD1") (pinfunction "CD_CD1") (pintype "bidirectional"))
    )
    (net (code "64") (name "unconnected-(U401-#RSTOUT-Pad14)") (class "Default")
      (node (ref "U401") (pin "14") (pinfunction "#RSTOUT_14") (pintype "bidirectional"))
    )
    (net (code "65") (name "unconnected-(U401-#TRST-Pad4)") (class "Default")
      (node (ref "U401") (pin "4") (pinfunction "#TRST_4") (pintype "bidirectional"))
    )
    (net (code "66") (name "unconnected-(U401-P0[4]{slash}I2SRX_CLK{slash}RD2{slash}CAP2[0]-Pad81)") (class "Default")
      (node (ref "U401") (pin "81") (pinfunction "P0[4]/I2SRX_CLK/RD2/CAP2[0]_81") (pintype "bidirectional"))
    )
    (net (code "67") (name "unconnected-(U401-P0[5]{slash}I2SRX_WS{slash}TD2{slash}CAP2[1]-Pad80)") (class "Default")
      (node (ref "U401") (pin "80") (pinfunction "P0[5]/I2SRX_WS/TD2/CAP2[1]_80") (pintype "bidirectional"))
    )
    (net (code "68") (name "unconnected-(U401-P0[10]{slash}TXD2{slash}SDA2{slash}MAT3[0]-Pad48)") (class "Default")
      (node (ref "U401") (pin "48") (pinfunction "P0[10]/TXD2/SDA2/MAT3[0]_48") (pintype "bidirectional"))
    )
    (net (code "69") (name "unconnected-(U401-P0[11]{slash}RXD2{slash}SCL2{slash}MAT3[1]-Pad49)") (class "Default")
      (node (ref "U401") (pin "49") (pinfunction "P0[11]/RXD2/SCL2/MAT3[1]_49") (pintype "bidirectional"))
    )
    (net (code "70") (name "unconnected-(U401-P0[17]{slash}CTS1{slash}MISO0{slash}MISO-Pad61)") (class "Default")
      (node (ref "U401") (pin "61") (pinfunction "P0[17]/CTS1/MISO0/MISO_61") (pintype "bidirectional"))
    )
    (net (code "71") (name "unconnected-(U401-P0[18]{slash}DCD1{slash}MOSI0{slash}MOSI-Pad60)") (class "Default")
      (node (ref "U401") (pin "60") (pinfunction "P0[18]/DCD1/MOSI0/MOSI_60") (pintype "bidirectional"))
    )
    (net (code "72") (name "unconnected-(U401-P0[21]{slash}RI1{slash}MCIPWR{slash}RD1-Pad57)") (class "Default")
      (node (ref "U401") (pin "57") (pinfunction "P0[21]/RI1/MCIPWR/RD1_57") (pintype "bidirectional"))
    )
    (net (code "73") (name "unconnected-(U401-P1[4]{slash}ENET_TX_EN-Pad93)") (class "Default")
      (node (ref "U401") (pin "93") (pinfunction "P1[4]/ENET_TX_EN_93") (pintype "bidirectional"))
    )
    (net (code "74") (name "unconnected-(U401-P1[8]{slash}ENET_CRS-Pad92)") (class "Default")
      (node (ref "U401") (pin "92") (pinfunction "P1[8]/ENET_CRS_92") (pintype "bidirectional"))
    )
    (net (code "75") (name "unconnected-(U401-P1[9]{slash}ENET_RXD0-Pad91)") (class "Default")
      (node (ref "U401") (pin "91") (pinfunction "P1[9]/ENET_RXD0_91") (pintype "bidirectional"))
    )
    (net (code "76") (name "unconnected-(U401-P1[10]{slash}ENET_RXD1-Pad90)") (class "Default")
      (node (ref "U401") (pin "90") (pinfunction "P1[10]/ENET_RXD1_90") (pintype "bidirectional"))
    )
    (net (code "77") (name "unconnected-(U401-P1[14]{slash}ENET_RX_ER-Pad89)") (class "Default")
      (node (ref "U401") (pin "89") (pinfunction "P1[14]/ENET_RX_ER_89") (pintype "bidirectional"))
    )
    (net (code "78") (name "unconnected-(U401-P1[15]{slash}ENET_REF_CLK-Pad88)") (class "Default")
      (node (ref "U401") (pin "88") (pinfunction "P1[15]/ENET_REF_CLK_88") (pintype "bidirectional"))
    )
    (net (code "79") (name "unconnected-(U401-P1[16]{slash}ENET_MDC-Pad87)") (class "Default")
      (node (ref "U401") (pin "87") (pinfunction "P1[16]/ENET_MDC_87") (pintype "bidirectional"))
    )
    (net (code "80") (name "unconnected-(U401-P1[17]{slash}ENET_MDIO-Pad86)") (class "Default")
      (node (ref "U401") (pin "86") (pinfunction "P1[17]/ENET_MDIO_86") (pintype "bidirectional"))
    )
    (net (code "81") (name "unconnected-(U401-P1[19]{slash}CAP1[1]-Pad33)") (class "Default")
      (node (ref "U401") (pin "33") (pinfunction "P1[19]/CAP1[1]_33") (pintype "bidirectional"))
    )
    (net (code "82") (name "unconnected-(U401-P1[20]{slash}PWM1[2]{slash}SCK0-Pad34)") (class "Default")
      (node (ref "U401") (pin "34") (pinfunction "P1[20]/PWM1[2]/SCK0_34") (pintype "bidirectional"))
    )
    (net (code "83") (name "unconnected-(U401-P1[21]{slash}PWM1[3]{slash}SSEL0-Pad35)") (class "Default")
      (node (ref "U401") (pin "35") (pinfunction "P1[21]/PWM1[3]/SSEL0_35") (pintype "bidirectional"))
    )
    (net (code "84") (name "unconnected-(U401-P1[22]{slash}MAT1[0]-Pad36)") (class "Default")
      (node (ref "U401") (pin "36") (pinfunction "P1[22]/MAT1[0]_36") (pintype "bidirectional"))
    )
    (net (code "85") (name "unconnected-(U401-P1[23]{slash}PWM1[4]{slash}MISO0-Pad37)") (class "Default")
      (node (ref "U401") (pin "37") (pinfunction "P1[23]/PWM1[4]/MISO0_37") (pintype "bidirectional"))
    )
    (net (code "86") (name "unconnected-(U401-P1[24]{slash}PWM1[5]{slash}MOSI0-Pad38)") (class "Default")
      (node (ref "U401") (pin "38") (pinfunction "P1[24]/PWM1[5]/MOSI0_38") (pintype "bidirectional"))
    )
    (net (code "87") (name "unconnected-(U401-P1[25]{slash}MAT1[1]-Pad39)") (class "Default")
      (node (ref "U401") (pin "39") (pinfunction "P1[25]/MAT1[1]_39") (pintype "bidirectional"))
    )
    (net (code "88") (name "unconnected-(U401-P1[28]{slash}PCAP1[0]{slash}MAT0[0]-Pad44)") (class "Default")
      (node (ref "U401") (pin "44") (pinfunction "P1[28]/PCAP1[0]/MAT0[0]_44") (pintype "bidirectional"))
    )
    (net (code "89") (name "unconnected-(U401-P1[29]{slash}PCAP1[1]{slash}MAT0[1]-Pad45)") (class "Default")
      (node (ref "U401") (pin "45") (pinfunction "P1[29]/PCAP1[1]/MAT0[1]_45") (pintype "bidirectional"))
    )
    (net (code "90") (name "unconnected-(U401-P2[6]{slash}PCAP1[0]{slash}RI1{slash}TRACEPKT1-Pad67)") (class "Default")
      (node (ref "U401") (pin "67") (pinfunction "P2[6]/PCAP1[0]/RI1/TRACEPKT1_67") (pintype "bidirectional"))
    )
    (net (code "91") (name "unconnected-(U401-P2[7]{slash}RD2{slash}RTS1{slash}TRACEPKT2-Pad66)") (class "Default")
      (node (ref "U401") (pin "66") (pinfunction "P2[7]/RD2/RTS1/TRACEPKT2_66") (pintype "bidirectional"))
    )
    (net (code "92") (name "unconnected-(U401-P2[8]{slash}TD2{slash}TXD2{slash}TRACEPKT3-Pad65)") (class "Default")
      (node (ref "U401") (pin "65") (pinfunction "P2[8]/TD2/TXD2/TRACEPKT3_65") (pintype "bidirectional"))
    )
    (net (code "93") (name "unconnected-(U401-P3[25]{slash}MAT0[0]{slash}PWM1[2]-Pad27)") (class "Default")
      (node (ref "U401") (pin "27") (pinfunction "P3[25]/MAT0[0]/PWM1[2]_27") (pintype "bidirectional"))
    )
    (net (code "94") (name "unconnected-(U401-P3[26]{slash}MAT0[1]{slash}PWM1[3]-Pad26)") (class "Default")
      (node (ref "U401") (pin "26") (pinfunction "P3[26]/MAT0[1]/PWM1[3]_26") (pintype "bidirectional"))
    )
    (net (code "95") (name "unconnected-(U401-P4[28]{slash}MAT2[0]{slash}TXD3-Pad82)") (class "Default")
      (node (ref "U401") (pin "82") (pinfunction "P4[28]/MAT2[0]/TXD3_82") (pintype "bidirectional"))
    )
    (net (code "96") (name "unconnected-(U401-P4[29]{slash}MAT2[1]{slash}RXD3-Pad85)") (class "Default")
      (node (ref "U401") (pin "85") (pinfunction "P4[29]/MAT2[1]/RXD3_85") (pintype "bidirectional"))
    )
    (net (code "97") (name "unconnected-(U401-RTCK-Pad100)") (class "Default")
      (node (ref "U401") (pin "100") (pinfunction "RTCK_100") (pintype "bidirectional"))
    )
    (net (code "98") (name "unconnected-(U401-RTCX1-Pad16)") (class "Default")
      (node (ref "U401") (pin "16") (pinfunction "RTCX1_16") (pintype "bidirectional"))
    )
    (net (code "99") (name "unconnected-(U401-RTCX2-Pad18)") (class "Default")
      (node (ref "U401") (pin "18") (pinfunction "RTCX2_18") (pintype "bidirectional"))
    )
    (net (code "100") (name "unconnected-(U401-TCK-Pad5)") (class "Default")
      (node (ref "U401") (pin "5") (pinfunction "TCK_5") (pintype "bidirectional"))
    )
    (net (code "101") (name "unconnected-(U401-TD0-Pad1)") (class "Default")
      (node (ref "U401") (pin "1") (pinfunction "TD0_1") (pintype "bidirectional"))
    )
    (net (code "102") (name "unconnected-(U401-TDI-Pad2)") (class "Default")
      (node (ref "U401") (pin "2") (pinfunction "TDI_2") (pintype "bidirectional"))
    )
    (net (code "103") (name "unconnected-(U401-TMS-Pad3)") (class "Default")
      (node (ref "U401") (pin "3") (pinfunction "TMS_3") (pintype "bidirectional"))
    )
  )
)
